# can_tester_1.net
KiCad netlist of a schematic drawn in EAGLE
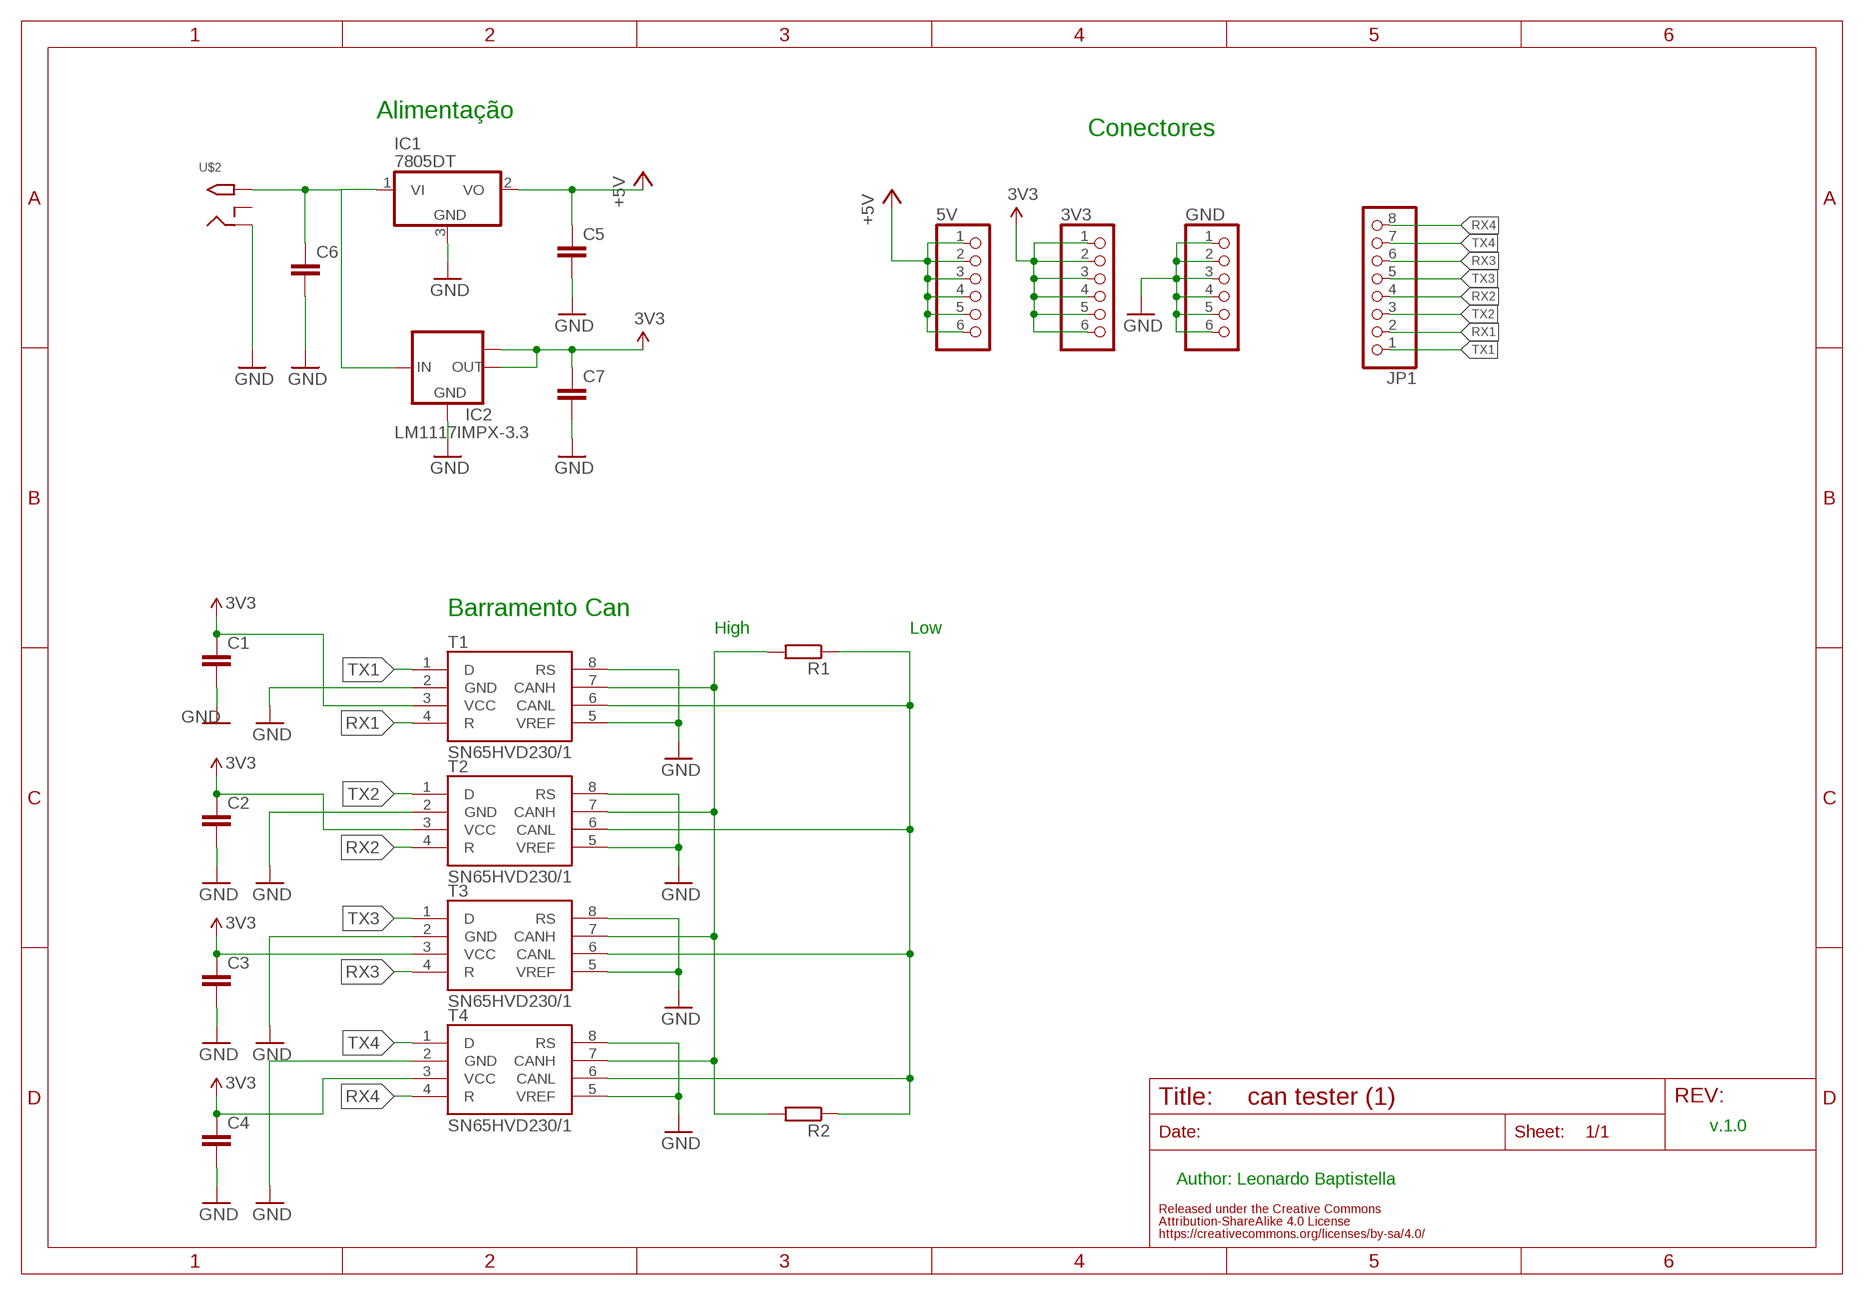
[diagram p0: schematic, sheet 1]

(export (version "E")
  (design (tool "Eeschema 10.0.6"))
  (components
    (comp (ref "3V3")
      (value "PINHD-1X6B")
      (footprint "eagle-import:1X06-BIG")
      (libsource (lib "eagle-import") (part "PINHD-1X6B"))
    )
    (comp (ref "5V")
      (value "PINHD-1X6B")
      (footprint "eagle-import:1X06-BIG")
      (libsource (lib "eagle-import") (part "PINHD-1X6B"))
    )
    (comp (ref "C1")
      (value "C-EUC1206K")
      (footprint "eagle-import:C1206K")
      (libsource (lib "eagle-import") (part "C-EUC1206K"))
    )
    (comp (ref "C2")
      (value "C-EUC1206K")
      (footprint "eagle-import:C1206K")
      (libsource (lib "eagle-import") (part "C-EUC1206K"))
    )
    (comp (ref "C3")
      (value "C-EUC1206K")
      (footprint "eagle-import:C1206K")
      (libsource (lib "eagle-import") (part "C-EUC1206K"))
    )
    (comp (ref "C4")
      (value "C-EUC1206K")
      (footprint "eagle-import:C1206K")
      (libsource (lib "eagle-import") (part "C-EUC1206K"))
    )
    (comp (ref "C5")
      (value "C-EUC1206K")
      (footprint "eagle-import:C1206K")
      (libsource (lib "eagle-import") (part "C-EUC1206K"))
    )
    (comp (ref "C6")
      (value "C-EUC1206K")
      (footprint "eagle-import:C1206K")
      (libsource (lib "eagle-import") (part "C-EUC1206K"))
    )
    (comp (ref "C7")
      (value "C-EUC1206K")
      (footprint "eagle-import:C1206K")
      (libsource (lib "eagle-import") (part "C-EUC1206K"))
    )
    (comp (ref "GND")
      (value "PINHD-1X6B")
      (footprint "eagle-import:1X06-BIG")
      (libsource (lib "eagle-import") (part "PINHD-1X6B"))
    )
    (comp (ref "IC1")
      (value "7805DT")
      (footprint "eagle-import:TO252")
      (libsource (lib "eagle-import") (part "78DT05"))
    )
    (comp (ref "IC2")
      (value "LM1117IMPX-3.3")
      (footprint "eagle-import:SOT223")
      (libsource (lib "eagle-import") (part "LM1117IMPX-3.3"))
    )
    (comp (ref "JP1")
      (value "PINHD-1X8BIG")
      (footprint "eagle-import:1X08-BIG")
      (libsource (lib "eagle-import") (part "PINHD-1X8BIG"))
    )
    (comp (ref "R1")
      (value "R-EU_0204/7")
      (footprint "eagle-import:0204_7")
      (libsource (lib "eagle-import") (part "R-EU_0204/7"))
    )
    (comp (ref "R2")
      (value "R-EU_0204/7")
      (footprint "eagle-import:0204_7")
      (libsource (lib "eagle-import") (part "R-EU_0204/7"))
    )
    (comp (ref "T1")
      (value "SN65HVD230/1")
      (footprint "eagle-import:SO8")
      (libsource (lib "eagle-import") (part "SN65HVD230/1"))
    )
    (comp (ref "T2")
      (value "SN65HVD230/1")
      (footprint "eagle-import:SO8")
      (libsource (lib "eagle-import") (part "SN65HVD230/1"))
    )
    (comp (ref "T3")
      (value "SN65HVD230/1")
      (footprint "eagle-import:SO8")
      (libsource (lib "eagle-import") (part "SN65HVD230/1"))
    )
    (comp (ref "T4")
      (value "SN65HVD230/1")
      (footprint "eagle-import:SO8")
      (libsource (lib "eagle-import") (part "SN65HVD230/1"))
    )
    (comp (ref "U$2")
      (value "2.1MMJACKTHM")
      (footprint "eagle-import:PJ-102A")
      (libsource (lib "eagle-import") (part "2.1MMJACKTHM"))
    )
  )
  (nets
    (net (code "1") (name "+5V") (class "Default")
      (node (ref "5V") (pin "1") (pinfunction "1_1") (pintype "passive"))
      (node (ref "5V") (pin "2") (pinfunction "2_2") (pintype "passive"))
      (node (ref "5V") (pin "3") (pinfunction "3_3") (pintype "passive"))
      (node (ref "5V") (pin "4") (pinfunction "4_4") (pintype "passive"))
      (node (ref "5V") (pin "5") (pinfunction "5_5") (pintype "passive"))
      (node (ref "5V") (pin "6") (pinfunction "6_6") (pintype "passive"))
      (node (ref "C5") (pin "1") (pinfunction "1_1") (pintype "passive"))
      (node (ref "IC1") (pin "2") (pinfunction "VO_2") (pintype "passive"))
    )
    (net (code "2") (name "3V3") (class "Default")
      (node (ref "3V3") (pin "1") (pinfunction "1_1") (pintype "passive"))
      (node (ref "3V3") (pin "2") (pinfunction "2_2") (pintype "passive"))
      (node (ref "3V3") (pin "3") (pinfunction "3_3") (pintype "passive"))
      (node (ref "3V3") (pin "4") (pinfunction "4_4") (pintype "passive"))
      (node (ref "3V3") (pin "5") (pinfunction "5_5") (pintype "passive"))
      (node (ref "3V3") (pin "6") (pinfunction "6_6") (pintype "passive"))
      (node (ref "C1") (pin "1") (pinfunction "1_1") (pintype "passive"))
      (node (ref "C2") (pin "1") (pinfunction "1_1") (pintype "passive"))
      (node (ref "C3") (pin "1") (pinfunction "1_1") (pintype "passive"))
      (node (ref "C4") (pin "1") (pinfunction "1_1") (pintype "passive"))
      (node (ref "C7") (pin "1") (pinfunction "1_1") (pintype "passive"))
      (node (ref "IC2") (pin "2") (pinfunction "OUT_2") (pintype "passive"))
      (node (ref "IC2") (pin "TAB") (pinfunction "OUT1_TAB") (pintype "passive"))
      (node (ref "T1") (pin "3") (pinfunction "VCC_3") (pintype "power_in"))
      (node (ref "T2") (pin "3") (pinfunction "VCC_3") (pintype "power_in"))
      (node (ref "T3") (pin "3") (pinfunction "VCC_3") (pintype "power_in"))
      (node (ref "T4") (pin "3") (pinfunction "VCC_3") (pintype "power_in"))
    )
    (net (code "3") (name "GND") (class "Default")
      (node (ref "C1") (pin "2") (pinfunction "2_2") (pintype "passive"))
      (node (ref "C2") (pin "2") (pinfunction "2_2") (pintype "passive"))
      (node (ref "C3") (pin "2") (pinfunction "2_2") (pintype "passive"))
      (node (ref "C4") (pin "2") (pinfunction "2_2") (pintype "passive"))
      (node (ref "C5") (pin "2") (pinfunction "2_2") (pintype "passive"))
      (node (ref "C6") (pin "2") (pinfunction "2_2") (pintype "passive"))
      (node (ref "C7") (pin "2") (pinfunction "2_2") (pintype "passive"))
      (node (ref "GND") (pin "1") (pinfunction "1_1") (pintype "passive"))
      (node (ref "GND") (pin "2") (pinfunction "2_2") (pintype "passive"))
      (node (ref "GND") (pin "3") (pinfunction "3_3") (pintype "passive"))
      (node (ref "GND") (pin "4") (pinfunction "4_4") (pintype "passive"))
      (node (ref "GND") (pin "5") (pinfunction "5_5") (pintype "passive"))
      (node (ref "GND") (pin "6") (pinfunction "6_6") (pintype "passive"))
      (node (ref "IC1") (pin "3") (pinfunction "GND_3") (pintype "passive"))
      (node (ref "IC2") (pin "1") (pinfunction "GND_1") (pintype "input"))
      (node (ref "T1") (pin "2") (pinfunction "GND_2") (pintype "power_in"))
      (node (ref "T1") (pin "5") (pinfunction "VREF_5") (pintype "bidirectional"))
      (node (ref "T1") (pin "8") (pinfunction "RS_8") (pintype "bidirectional"))
      (node (ref "T2") (pin "2") (pinfunction "GND_2") (pintype "power_in"))
      (node (ref "T2") (pin "5") (pinfunction "VREF_5") (pintype "bidirectional"))
      (node (ref "T2") (pin "8") (pinfunction "RS_8") (pintype "bidirectional"))
      (node (ref "T3") (pin "2") (pinfunction "GND_2") (pintype "power_in"))
      (node (ref "T3") (pin "5") (pinfunction "VREF_5") (pintype "bidirectional"))
      (node (ref "T3") (pin "8") (pinfunction "RS_8") (pintype "bidirectional"))
      (node (ref "T4") (pin "2") (pinfunction "GND_2") (pintype "power_in"))
      (node (ref "T4") (pin "5") (pinfunction "VREF_5") (pintype "bidirectional"))
      (node (ref "T4") (pin "8") (pinfunction "RS_8") (pintype "bidirectional"))
      (node (ref "U$2") (pin "RING") (pinfunction "RING_RING") (pintype "bidirectional"))
    )
    (net (code "4") (name "Net-(IC1-VI)") (class "Default")
      (node (ref "C6") (pin "1") (pinfunction "1_1") (pintype "passive"))
      (node (ref "IC1") (pin "1") (pinfunction "VI_1") (pintype "input"))
      (node (ref "IC2") (pin "3") (pinfunction "IN_3") (pintype "input"))
      (node (ref "U$2") (pin "TIP") (pinfunction "TIP_TIP") (pintype "bidirectional"))
    )
    (net (code "5") (name "Net-(T1-CANH)") (class "Default")
      (node (ref "R1") (pin "2") (pinfunction "2_2") (pintype "passive"))
      (node (ref "R2") (pin "2") (pinfunction "2_2") (pintype "passive"))
      (node (ref "T1") (pin "7") (pinfunction "CANH_7") (pintype "bidirectional"))
      (node (ref "T2") (pin "7") (pinfunction "CANH_7") (pintype "bidirectional"))
      (node (ref "T3") (pin "7") (pinfunction "CANH_7") (pintype "bidirectional"))
      (node (ref "T4") (pin "7") (pinfunction "CANH_7") (pintype "bidirectional"))
    )
    (net (code "6") (name "Net-(T1-CANL)") (class "Default")
      (node (ref "R1") (pin "1") (pinfunction "1_1") (pintype "passive"))
      (node (ref "R2") (pin "1") (pinfunction "1_1") (pintype "passive"))
      (node (ref "T1") (pin "6") (pinfunction "CANL_6") (pintype "bidirectional"))
      (node (ref "T2") (pin "6") (pinfunction "CANL_6") (pintype "bidirectional"))
      (node (ref "T3") (pin "6") (pinfunction "CANL_6") (pintype "bidirectional"))
      (node (ref "T4") (pin "6") (pinfunction "CANL_6") (pintype "bidirectional"))
    )
    (net (code "7") (name "RX1") (class "Default")
      (node (ref "JP1") (pin "2") (pinfunction "2_2") (pintype "passive"))
      (node (ref "T1") (pin "4") (pinfunction "R_4") (pintype "bidirectional"))
    )
    (net (code "8") (name "RX2") (class "Default")
      (node (ref "JP1") (pin "4") (pinfunction "4_4") (pintype "passive"))
      (node (ref "T2") (pin "4") (pinfunction "R_4") (pintype "bidirectional"))
    )
    (net (code "9") (name "RX3") (class "Default")
      (node (ref "JP1") (pin "6") (pinfunction "6_6") (pintype "passive"))
      (node (ref "T3") (pin "4") (pinfunction "R_4") (pintype "bidirectional"))
    )
    (net (code "10") (name "RX4") (class "Default")
      (node (ref "JP1") (pin "8") (pinfunction "8_8") (pintype "passive"))
      (node (ref "T4") (pin "4") (pinfunction "R_4") (pintype "bidirectional"))
    )
    (net (code "11") (name "TX1") (class "Default")
      (node (ref "JP1") (pin "1") (pinfunction "1_1") (pintype "passive"))
      (node (ref "T1") (pin "1") (pinfunction "D_1") (pintype "bidirectional"))
    )
    (net (code "12") (name "TX2") (class "Default")
      (node (ref "JP1") (pin "3") (pinfunction "3_3") (pintype "passive"))
      (node (ref "T2") (pin "1") (pinfunction "D_1") (pintype "bidirectional"))
    )
    (net (code "13") (name "TX3") (class "Default")
      (node (ref "JP1") (pin "5") (pinfunction "5_5") (pintype "passive"))
      (node (ref "T3") (pin "1") (pinfunction "D_1") (pintype "bidirectional"))
    )
    (net (code "14") (name "TX4") (class "Default")
      (node (ref "JP1") (pin "7") (pinfunction "7_7") (pintype "passive"))
      (node (ref "T4") (pin "1") (pinfunction "D_1") (pintype "bidirectional"))
    )
    (net (code "15") (name "unconnected-(U$2-PadRING_SW)") (class "Default")
      (node (ref "U$2") (pin "RING_SW") (pinfunction "RING_SW_RING_SW") (pintype "bidirectional"))
    )
  )
)
